# Strain_guage.net
KiCad netlist of a schematic drawn in EAGLE
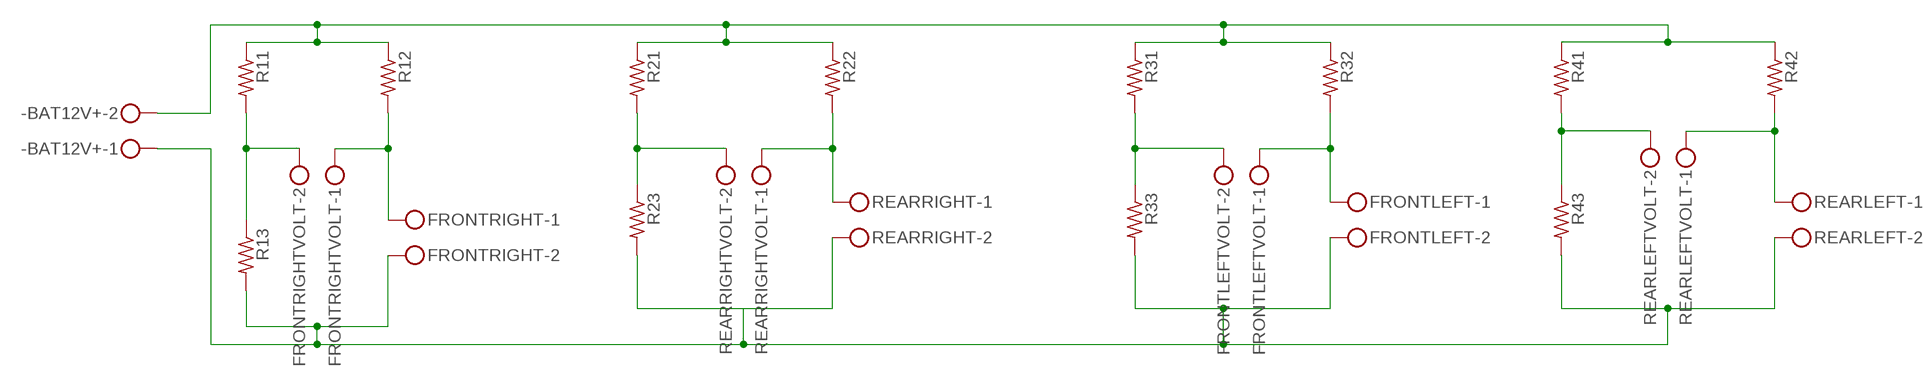
[diagram p0: schematic, sheet 1]

(export (version "E")
  (design (tool "Eeschema 10.0.6"))
  (components
    (comp (ref "-BAT12V+")
      (value "MKDSN1,5/2-5,08")
      (footprint "eagle-import:MKDSN1,5_2-5,08")
      (libsource (lib "eagle-import") (part "MKDSN1,5/2-5,08"))
    )
    (comp (ref "FRONTLEFT")
      (value "MKDSN1,5/2-5,08")
      (footprint "eagle-import:MKDSN1,5_2-5,08")
      (libsource (lib "eagle-import") (part "MKDSN1,5/2-5,08"))
    )
    (comp (ref "FRONTLEFTVOLT")
      (value "MKDSN1,5/2-5,08")
      (footprint "eagle-import:MKDSN1,5_2-5,08")
      (libsource (lib "eagle-import") (part "MKDSN1,5/2-5,08"))
    )
    (comp (ref "FRONTRIGHT")
      (value "MKDSN1,5/2-5,08")
      (footprint "eagle-import:MKDSN1,5_2-5,08")
      (libsource (lib "eagle-import") (part "MKDSN1,5/2-5,08"))
    )
    (comp (ref "FRONTRIGHTVOLT")
      (value "MKDSN1,5/2-5,08")
      (footprint "eagle-import:MKDSN1,5_2-5,08")
      (libsource (lib "eagle-import") (part "MKDSN1,5/2-5,08"))
    )
    (comp (ref "R11")
      (value "R-US_0204/7")
      (footprint "eagle-import:0204_7")
      (libsource (lib "eagle-import") (part "R-US_0204/7"))
    )
    (comp (ref "R12")
      (value "R-US_0204/7")
      (footprint "eagle-import:0204_7")
      (libsource (lib "eagle-import") (part "R-US_0204/7"))
    )
    (comp (ref "R13")
      (value "R-US_0204/7")
      (footprint "eagle-import:0204_7")
      (libsource (lib "eagle-import") (part "R-US_0204/7"))
    )
    (comp (ref "R21")
      (value "R-US_0204/7")
      (footprint "eagle-import:0204_7")
      (libsource (lib "eagle-import") (part "R-US_0204/7"))
    )
    (comp (ref "R22")
      (value "R-US_0204/7")
      (footprint "eagle-import:0204_7")
      (libsource (lib "eagle-import") (part "R-US_0204/7"))
    )
    (comp (ref "R23")
      (value "R-US_0204/7")
      (footprint "eagle-import:0204_7")
      (libsource (lib "eagle-import") (part "R-US_0204/7"))
    )
    (comp (ref "R31")
      (value "R-US_0204/7")
      (footprint "eagle-import:0204_7")
      (libsource (lib "eagle-import") (part "R-US_0204/7"))
    )
    (comp (ref "R32")
      (value "R-US_0204/7")
      (footprint "eagle-import:0204_7")
      (libsource (lib "eagle-import") (part "R-US_0204/7"))
    )
    (comp (ref "R33")
      (value "R-US_0204/7")
      (footprint "eagle-import:0204_7")
      (libsource (lib "eagle-import") (part "R-US_0204/7"))
    )
    (comp (ref "R41")
      (value "R-US_0204/7")
      (footprint "eagle-import:0204_7")
      (libsource (lib "eagle-import") (part "R-US_0204/7"))
    )
    (comp (ref "R42")
      (value "R-US_0204/7")
      (footprint "eagle-import:0204_7")
      (libsource (lib "eagle-import") (part "R-US_0204/7"))
    )
    (comp (ref "R43")
      (value "R-US_0204/7")
      (footprint "eagle-import:0204_7")
      (libsource (lib "eagle-import") (part "R-US_0204/7"))
    )
    (comp (ref "REARLEFT")
      (value "MKDSN1,5/2-5,08")
      (footprint "eagle-import:MKDSN1,5_2-5,08")
      (libsource (lib "eagle-import") (part "MKDSN1,5/2-5,08"))
    )
    (comp (ref "REARLEFTVOLT")
      (value "MKDSN1,5/2-5,08")
      (footprint "eagle-import:MKDSN1,5_2-5,08")
      (libsource (lib "eagle-import") (part "MKDSN1,5/2-5,08"))
    )
    (comp (ref "REARRIGHT")
      (value "MKDSN1,5/2-5,08")
      (footprint "eagle-import:MKDSN1,5_2-5,08")
      (libsource (lib "eagle-import") (part "MKDSN1,5/2-5,08"))
    )
    (comp (ref "REARRIGHTVOLT")
      (value "MKDSN1,5/2-5,08")
      (footprint "eagle-import:MKDSN1,5_2-5,08")
      (libsource (lib "eagle-import") (part "MKDSN1,5/2-5,08"))
    )
  )
  (nets
    (net (code "1") (name "Net-(-BAT12V+A-KL)") (class "Default")
      (node (ref "-BAT12V+") (pin "1") (pinfunction "KL_1") (pintype "passive"))
      (node (ref "FRONTLEFT") (pin "2") (pinfunction "KL_2") (pintype "passive"))
      (node (ref "FRONTRIGHT") (pin "2") (pinfunction "KL_2") (pintype "passive"))
      (node (ref "R13") (pin "2") (pinfunction "2_2") (pintype "passive"))
      (node (ref "R23") (pin "2") (pinfunction "2_2") (pintype "passive"))
      (node (ref "R33") (pin "2") (pinfunction "2_2") (pintype "passive"))
      (node (ref "R43") (pin "2") (pinfunction "2_2") (pintype "passive"))
      (node (ref "REARLEFT") (pin "2") (pinfunction "KL_2") (pintype "passive"))
      (node (ref "REARRIGHT") (pin "2") (pinfunction "KL_2") (pintype "passive"))
    )
    (net (code "2") (name "Net-(-BAT12V+B-KL)") (class "Default")
      (node (ref "-BAT12V+") (pin "2") (pinfunction "KL_2") (pintype "passive"))
      (node (ref "R11") (pin "1") (pinfunction "1_1") (pintype "passive"))
      (node (ref "R12") (pin "1") (pinfunction "1_1") (pintype "passive"))
      (node (ref "R21") (pin "1") (pinfunction "1_1") (pintype "passive"))
      (node (ref "R22") (pin "1") (pinfunction "1_1") (pintype "passive"))
      (node (ref "R31") (pin "1") (pinfunction "1_1") (pintype "passive"))
      (node (ref "R32") (pin "1") (pinfunction "1_1") (pintype "passive"))
      (node (ref "R41") (pin "1") (pinfunction "1_1") (pintype "passive"))
      (node (ref "R42") (pin "1") (pinfunction "1_1") (pintype "passive"))
    )
    (net (code "3") (name "Net-(FRONTLEFTA-KL)") (class "Default")
      (node (ref "FRONTLEFT") (pin "1") (pinfunction "KL_1") (pintype "passive"))
      (node (ref "FRONTLEFTVOLT") (pin "1") (pinfunction "KL_1") (pintype "passive"))
      (node (ref "R32") (pin "2") (pinfunction "2_2") (pintype "passive"))
    )
    (net (code "4") (name "Net-(FRONTLEFTVOLTB-KL)") (class "Default")
      (node (ref "FRONTLEFTVOLT") (pin "2") (pinfunction "KL_2") (pintype "passive"))
      (node (ref "R31") (pin "2") (pinfunction "2_2") (pintype "passive"))
      (node (ref "R33") (pin "1") (pinfunction "1_1") (pintype "passive"))
    )
    (net (code "5") (name "Net-(FRONTRIGHTA-KL)") (class "Default")
      (node (ref "FRONTRIGHT") (pin "1") (pinfunction "KL_1") (pintype "passive"))
      (node (ref "FRONTRIGHTVOLT") (pin "1") (pinfunction "KL_1") (pintype "passive"))
      (node (ref "R12") (pin "2") (pinfunction "2_2") (pintype "passive"))
    )
    (net (code "6") (name "Net-(FRONTRIGHTVOLTB-KL)") (class "Default")
      (node (ref "FRONTRIGHTVOLT") (pin "2") (pinfunction "KL_2") (pintype "passive"))
      (node (ref "R11") (pin "2") (pinfunction "2_2") (pintype "passive"))
      (node (ref "R13") (pin "1") (pinfunction "1_1") (pintype "passive"))
    )
    (net (code "7") (name "Net-(REARLEFTA-KL)") (class "Default")
      (node (ref "R42") (pin "2") (pinfunction "2_2") (pintype "passive"))
      (node (ref "REARLEFT") (pin "1") (pinfunction "KL_1") (pintype "passive"))
      (node (ref "REARLEFTVOLT") (pin "1") (pinfunction "KL_1") (pintype "passive"))
    )
    (net (code "8") (name "Net-(REARLEFTVOLTB-KL)") (class "Default")
      (node (ref "R41") (pin "2") (pinfunction "2_2") (pintype "passive"))
      (node (ref "R43") (pin "1") (pinfunction "1_1") (pintype "passive"))
      (node (ref "REARLEFTVOLT") (pin "2") (pinfunction "KL_2") (pintype "passive"))
    )
    (net (code "9") (name "Net-(REARRIGHTA-KL)") (class "Default")
      (node (ref "R22") (pin "2") (pinfunction "2_2") (pintype "passive"))
      (node (ref "REARRIGHT") (pin "1") (pinfunction "KL_1") (pintype "passive"))
      (node (ref "REARRIGHTVOLT") (pin "1") (pinfunction "KL_1") (pintype "passive"))
    )
    (net (code "10") (name "Net-(REARRIGHTVOLTB-KL)") (class "Default")
      (node (ref "R21") (pin "2") (pinfunction "2_2") (pintype "passive"))
      (node (ref "R23") (pin "1") (pinfunction "1_1") (pintype "passive"))
      (node (ref "REARRIGHTVOLT") (pin "2") (pinfunction "KL_2") (pintype "passive"))
    )
  )
)
